# RPi-HAT_BUS-Controller_V0_4.net
KiCad netlist of a schematic drawn in EAGLE
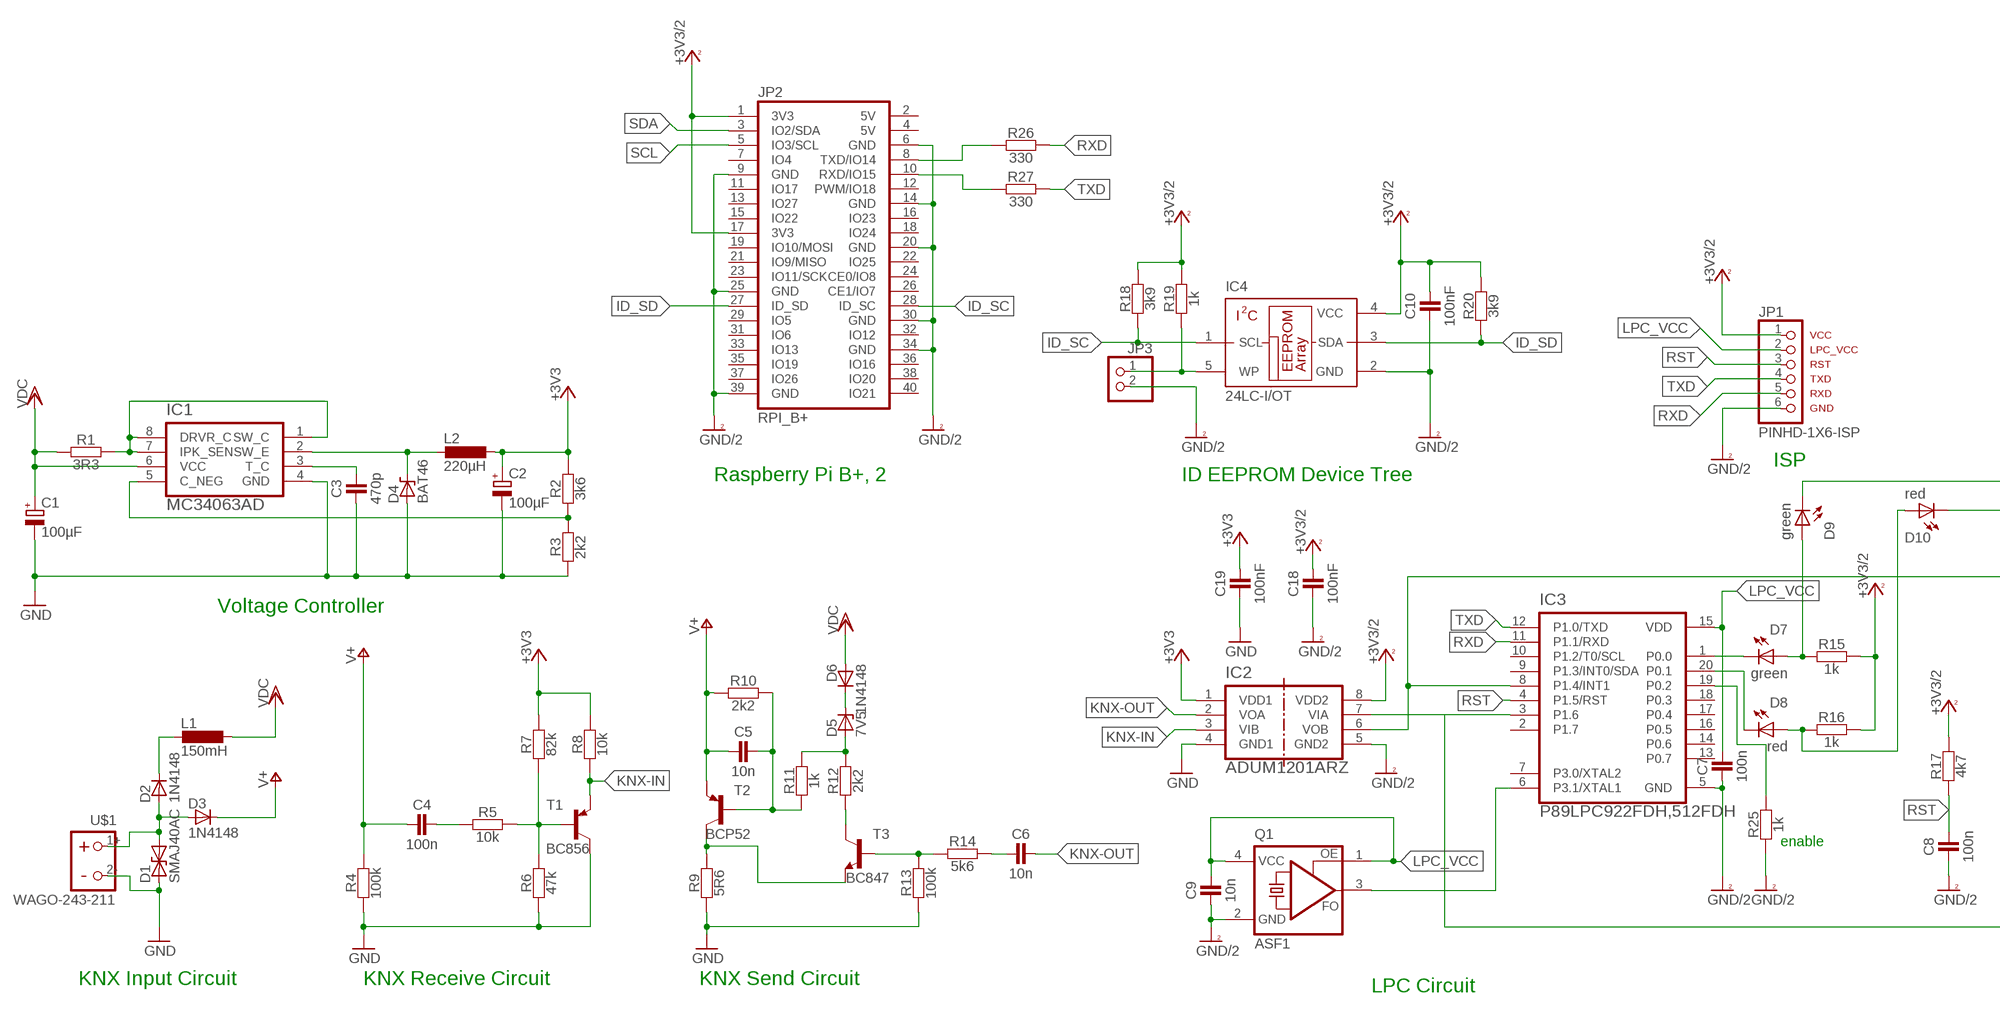
[diagram p0: schematic, sheet 1, part 1 of 2]
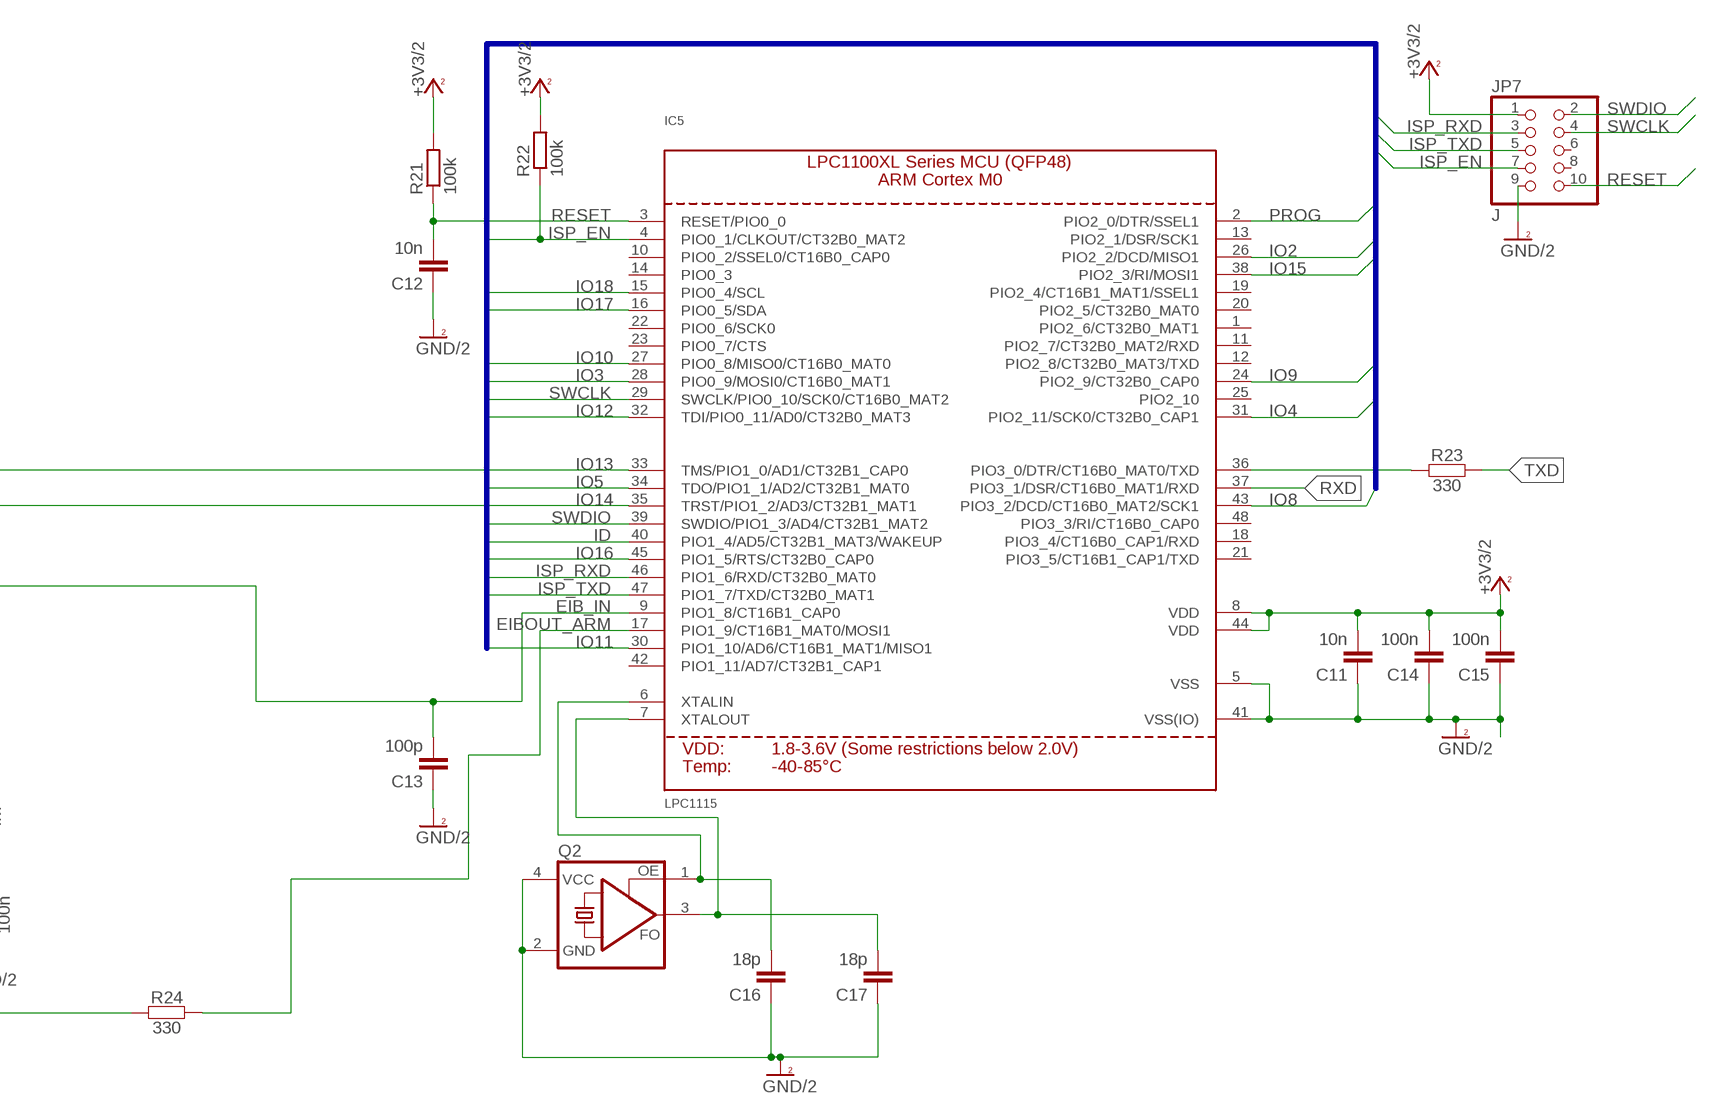
[diagram p1: schematic, sheet 1, part 2 of 2]

(export (version "E")
  (design (tool "Eeschema 10.0.6"))
  (components
    (comp (ref "C1")
      (value "100µF")
      (footprint "eagle-import:PANASONIC_D")
      (libsource (lib "eagle-import") (part "100µF,35V"))
    )
    (comp (ref "C2")
      (value "100µF")
      (footprint "eagle-import:PANASONIC_C")
      (libsource (lib "eagle-import") (part "100µF,6.3V"))
    )
    (comp (ref "C3")
      (value "470p")
      (footprint "eagle-import:R1206")
      (libsource (lib "eagle-import") (part "CAPACITORC1206"))
    )
    (comp (ref "C4")
      (value "100n")
      (footprint "eagle-import:R1206")
      (libsource (lib "eagle-import") (part "CAPACITORC1206"))
    )
    (comp (ref "C5")
      (value "10n")
      (footprint "eagle-import:R1206")
      (libsource (lib "eagle-import") (part "CAPACITORC1206"))
    )
    (comp (ref "C6")
      (value "10n")
      (footprint "eagle-import:R1206")
      (libsource (lib "eagle-import") (part "CAPACITORC1206"))
    )
    (comp (ref "C7")
      (value "100n")
      (footprint "eagle-import:R1206")
      (libsource (lib "eagle-import") (part "CAPACITORC1206"))
    )
    (comp (ref "C8")
      (value "100n")
      (footprint "eagle-import:R1206")
      (libsource (lib "eagle-import") (part "CAPACITORC1206"))
    )
    (comp (ref "C9")
      (value "10n")
      (footprint "eagle-import:R1206")
      (libsource (lib "eagle-import") (part "CAPACITORC1206"))
    )
    (comp (ref "C10")
      (value "100nF")
      (footprint "eagle-import:R1206")
      (libsource (lib "eagle-import") (part "CAPACITORC1206"))
    )
    (comp (ref "C11")
      (value "10n")
      (footprint "eagle-import:C1206")
      (libsource (lib "eagle-import") (part "C-EUC1206"))
    )
    (comp (ref "C12")
      (value "10n")
      (footprint "eagle-import:C1206")
      (libsource (lib "eagle-import") (part "C-EUC1206"))
    )
    (comp (ref "C13")
      (value "100p")
      (footprint "eagle-import:C1206")
      (libsource (lib "eagle-import") (part "C-EUC1206"))
    )
    (comp (ref "C14")
      (value "100n")
      (footprint "eagle-import:C1206")
      (libsource (lib "eagle-import") (part "C-EUC1206"))
    )
    (comp (ref "C15")
      (value "100n")
      (footprint "eagle-import:C1206")
      (libsource (lib "eagle-import") (part "C-EUC1206"))
    )
    (comp (ref "C16")
      (value "18p")
      (footprint "eagle-import:C1206")
      (libsource (lib "eagle-import") (part "C-EUC1206"))
    )
    (comp (ref "C17")
      (value "18p")
      (footprint "eagle-import:C1206")
      (libsource (lib "eagle-import") (part "C-EUC1206"))
    )
    (comp (ref "C18")
      (value "100nF")
      (footprint "eagle-import:R1206")
      (libsource (lib "eagle-import") (part "CAPACITORC1206"))
    )
    (comp (ref "C19")
      (value "100nF")
      (footprint "eagle-import:R1206")
      (libsource (lib "eagle-import") (part "CAPACITORC1206"))
    )
    (comp (ref "D1")
      (value "SMAJ40AC")
      (footprint "eagle-import:DO-214AC")
      (libsource (lib "eagle-import") (part "SMAJ40AC"))
    )
    (comp (ref "D2")
      (value "1N4148")
      (footprint "eagle-import:MINIMELF")
      (libsource (lib "eagle-import") (part "1N4148MINIMELF"))
    )
    (comp (ref "D3")
      (value "1N4148")
      (footprint "eagle-import:MINIMELF")
      (libsource (lib "eagle-import") (part "1N4148MINIMELF"))
    )
    (comp (ref "D4")
      (value "BAT46")
      (footprint "eagle-import:MINIMELF")
      (libsource (lib "eagle-import") (part "BAT46"))
    )
    (comp (ref "D5")
      (value "7V5")
      (footprint "eagle-import:MINIMELF")
      (libsource (lib "eagle-import") (part "Z-DIODE"))
    )
    (comp (ref "D6")
      (value "1N4148")
      (footprint "eagle-import:MINIMELF")
      (libsource (lib "eagle-import") (part "Diode_for_Selfbus-Projects_1N4148MINIMELF"))
    )
    (comp (ref "D7")
      (value "green")
      (footprint "eagle-import:CHIPLED_1206")
      (libsource (lib "eagle-import") (part "LED1206"))
    )
    (comp (ref "D8")
      (value "red")
      (footprint "eagle-import:CHIPLED_1206")
      (libsource (lib "eagle-import") (part "LED1206"))
    )
    (comp (ref "D9")
      (value "green")
      (footprint "eagle-import:CHIPLED_1206")
      (libsource (lib "eagle-import") (part "LED1206"))
    )
    (comp (ref "D10")
      (value "red")
      (footprint "eagle-import:CHIPLED_1206")
      (libsource (lib "eagle-import") (part "LED1206"))
    )
    (comp (ref "IC1")
      (value "MC34063AD")
      (footprint "eagle-import:SOIC127P600X175-8N")
      (libsource (lib "eagle-import") (part "MC34063AD"))
    )
    (comp (ref "IC2")
      (value "ADUM1201ARZ")
      (footprint "eagle-import:SOIC127P600X175-8N")
      (libsource (lib "eagle-import") (part "ADUM1201ARZ"))
    )
    (comp (ref "IC3")
      (value "P89LPC922FDH,512FDH")
      (footprint "eagle-import:SOP65P640X110-20N")
      (fields (field (name "MPN") "P89LPC922FDH,512"))
      (libsource (lib "eagle-import") (part "P89LPC922FDH,512FDH"))
    )
    (comp (ref "IC4")
      (value "24LC-I/OT")
      (footprint "eagle-import:SOT23-5")
      (libsource (lib "eagle-import") (part "24LC-I/OT"))
    )
    (comp (ref "IC5")
      (value "LPC1115")
      (footprint "eagle-import:LQFP48")
      (libsource (lib "eagle-import") (part "LPC1113/4/5_QFP48_XLSERIES"))
    )
    (comp (ref "JP1")
      (value "PINHD-1X6-ISP")
      (footprint "eagle-import:1X06")
      (libsource (lib "eagle-import") (part "PINHD-1X6-ISP"))
    )
    (comp (ref "JP2")
      (value "RPI_B+")
      (footprint "eagle-import:RPI-B+HAT")
      (libsource (lib "eagle-import") (part "RPI_B+"))
    )
    (comp (ref "JP3")
      (value "PINHD-1X2")
      (footprint "eagle-import:1X02")
      (libsource (lib "eagle-import") (part "PINHD-1X2"))
    )
    (comp (ref "JP7")
      (value "J")
      (footprint "eagle-import:2X05M")
      (libsource (lib "eagle-import") (part "PINHD-2X05_2.00"))
    )
    (comp (ref "L1")
      (value "150mH")
      (footprint "eagle-import:11P-L1")
      (libsource (lib "eagle-import") (part "150MH-L11PL1"))
    )
    (comp (ref "L2")
      (value "220µH")
      (footprint "eagle-import:2200-11.43")
      (libsource (lib "eagle-import") (part "220µH-SMCC11.43"))
    )
    (comp (ref "Q1")
      (value "ASF1")
      (footprint "eagle-import:ASF")
      (libsource (lib "eagle-import") (part "ASF1"))
    )
    (comp (ref "Q2")
      (value "ASFL")
      (footprint "eagle-import:ASF")
      (libsource (lib "eagle-import") (part "crystal_ASFL"))
    )
    (comp (ref "R1")
      (value "3R3")
      (footprint "eagle-import:R1206")
      (libsource (lib "eagle-import") (part "RESISTORR1206"))
    )
    (comp (ref "R2")
      (value "3k6")
      (footprint "eagle-import:R1206")
      (libsource (lib "eagle-import") (part "RESISTORR1206"))
    )
    (comp (ref "R3")
      (value "2k2")
      (footprint "eagle-import:R1206")
      (libsource (lib "eagle-import") (part "RESISTORR1206"))
    )
    (comp (ref "R4")
      (value "100k")
      (footprint "eagle-import:R1206")
      (libsource (lib "eagle-import") (part "RESISTORR1206"))
    )
    (comp (ref "R5")
      (value "10k")
      (footprint "eagle-import:R1206")
      (libsource (lib "eagle-import") (part "RESISTORR1206"))
    )
    (comp (ref "R6")
      (value "47k")
      (footprint "eagle-import:R1206")
      (libsource (lib "eagle-import") (part "RESISTORR1206"))
    )
    (comp (ref "R7")
      (value "82k")
      (footprint "eagle-import:R1206")
      (libsource (lib "eagle-import") (part "RESISTORR1206"))
    )
    (comp (ref "R8")
      (value "10k")
      (footprint "eagle-import:R1206")
      (libsource (lib "eagle-import") (part "RESISTORR1206"))
    )
    (comp (ref "R9")
      (value "5R6")
      (footprint "eagle-import:R1206")
      (libsource (lib "eagle-import") (part "RESISTORR1206"))
    )
    (comp (ref "R10")
      (value "2k2")
      (footprint "eagle-import:R1206")
      (libsource (lib "eagle-import") (part "RESISTORR1206"))
    )
    (comp (ref "R11")
      (value "1k")
      (footprint "eagle-import:R1206")
      (libsource (lib "eagle-import") (part "RESISTORR1206"))
    )
    (comp (ref "R12")
      (value "2k2")
      (footprint "eagle-import:R1206")
      (libsource (lib "eagle-import") (part "RESISTORR1206"))
    )
    (comp (ref "R13")
      (value "100k")
      (footprint "eagle-import:R1206")
      (libsource (lib "eagle-import") (part "RESISTORR1206"))
    )
    (comp (ref "R14")
      (value "5k6")
      (footprint "eagle-import:R1206")
      (libsource (lib "eagle-import") (part "RESISTORR1206"))
    )
    (comp (ref "R15")
      (value "1k")
      (footprint "eagle-import:R1206")
      (libsource (lib "eagle-import") (part "RESISTORR1206"))
    )
    (comp (ref "R16")
      (value "1k")
      (footprint "eagle-import:R1206")
      (libsource (lib "eagle-import") (part "RESISTORR1206"))
    )
    (comp (ref "R17")
      (value "4k7")
      (footprint "eagle-import:R1206")
      (libsource (lib "eagle-import") (part "RESISTORR1206"))
    )
    (comp (ref "R18")
      (value "3k9")
      (footprint "eagle-import:R1206")
      (libsource (lib "eagle-import") (part "RESISTORR1206"))
    )
    (comp (ref "R19")
      (value "1k")
      (footprint "eagle-import:R1206")
      (libsource (lib "eagle-import") (part "RESISTORR1206"))
    )
    (comp (ref "R20")
      (value "3k9")
      (footprint "eagle-import:R1206")
      (libsource (lib "eagle-import") (part "RESISTORR1206"))
    )
    (comp (ref "R21")
      (value "100k")
      (footprint "eagle-import:R1206")
      (libsource (lib "eagle-import") (part "R-EU_R1206"))
    )
    (comp (ref "R22")
      (value "100k")
      (footprint "eagle-import:R1206")
      (libsource (lib "eagle-import") (part "R-EU_R1206"))
    )
    (comp (ref "R23")
      (value "330")
      (footprint "eagle-import:R1206")
      (libsource (lib "eagle-import") (part "RESISTORR1206"))
    )
    (comp (ref "R24")
      (value "330")
      (footprint "eagle-import:R1206")
      (libsource (lib "eagle-import") (part "RESISTORR1206"))
    )
    (comp (ref "R25")
      (value "1k")
      (footprint "eagle-import:R1206")
      (libsource (lib "eagle-import") (part "RESISTORR1206"))
    )
    (comp (ref "R26")
      (value "330")
      (footprint "eagle-import:R1206")
      (libsource (lib "eagle-import") (part "RESISTORR1206"))
    )
    (comp (ref "R27")
      (value "330")
      (footprint "eagle-import:R1206")
      (libsource (lib "eagle-import") (part "RESISTORR1206"))
    )
    (comp (ref "T1")
      (value "BC856")
      (footprint "eagle-import:SOT23")
      (libsource (lib "eagle-import") (part "PNPBC856"))
    )
    (comp (ref "T2")
      (value "BCP52")
      (footprint "eagle-import:SOT223")
      (libsource (lib "eagle-import") (part "PNPBCP52"))
    )
    (comp (ref "T3")
      (value "BC847")
      (footprint "eagle-import:SOT23")
      (libsource (lib "eagle-import") (part "NPN-BC847"))
    )
    (comp (ref "U$1")
      (value "WAGO-243-211")
      (footprint "eagle-import:WAGO-243-211")
      (libsource (lib "eagle-import") (part "WAGO-243-211"))
    )
  )
  (nets
    (net (code "1") (name "+3V3") (class "Default")
      (node (ref "C19") (pin "2") (pinfunction "2_2") (pintype "passive"))
      (node (ref "C2") (pin "+") (pinfunction "+_+") (pintype "passive"))
      (node (ref "IC2") (pin "1") (pinfunction "VDD1_1") (pintype "power_in"))
      (node (ref "L2") (pin "1") (pinfunction "1_1") (pintype "passive"))
      (node (ref "R2") (pin "2") (pinfunction "2_2") (pintype "passive"))
      (node (ref "R7") (pin "2") (pinfunction "2_2") (pintype "passive"))
      (node (ref "R8") (pin "2") (pinfunction "2_2") (pintype "passive"))
    )
    (net (code "2") (name "+3V3{slash}2") (class "Default")
      (node (ref "C10") (pin "2") (pinfunction "2_2") (pintype "passive"))
      (node (ref "C11") (pin "2") (pinfunction "2_2") (pintype "passive"))
      (node (ref "C14") (pin "2") (pinfunction "2_2") (pintype "passive"))
      (node (ref "C15") (pin "2") (pinfunction "2_2") (pintype "passive"))
      (node (ref "C18") (pin "2") (pinfunction "2_2") (pintype "passive"))
      (node (ref "IC2") (pin "8") (pinfunction "VDD2_8") (pintype "power_in"))
      (node (ref "IC4") (pin "4") (pinfunction "VCC_4") (pintype "power_in"))
      (node (ref "IC5") (pin "44") (pinfunction "VDD_44") (pintype "power_in"))
      (node (ref "IC5") (pin "8") (pinfunction "VDD_8") (pintype "power_in"))
      (node (ref "JP1") (pin "1") (pinfunction "1_1") (pintype "passive"))
      (node (ref "JP2") (pin "1") (pinfunction "3V3_1") (pintype "passive"))
      (node (ref "JP2") (pin "17") (pinfunction "3V3_17") (pintype "passive"))
      (node (ref "JP7") (pin "1") (pinfunction "1_1") (pintype "passive"))
      (node (ref "R15") (pin "2") (pinfunction "2_2") (pintype "passive"))
      (node (ref "R16") (pin "2") (pinfunction "2_2") (pintype "passive"))
      (node (ref "R17") (pin "2") (pinfunction "2_2") (pintype "passive"))
      (node (ref "R18") (pin "2") (pinfunction "2_2") (pintype "passive"))
      (node (ref "R19") (pin "2") (pinfunction "2_2") (pintype "passive"))
      (node (ref "R20") (pin "2") (pinfunction "2_2") (pintype "passive"))
      (node (ref "R21") (pin "2") (pinfunction "2_2") (pintype "passive"))
      (node (ref "R22") (pin "2") (pinfunction "2_2") (pintype "passive"))
    )
    (net (code "3") (name "/EIBOUT_ARM") (class "Default")
      (node (ref "IC5") (pin "17") (pinfunction "PIO1_9/CT16B1_MAT0/MOSI1_17") (pintype "bidirectional"))
      (node (ref "R24") (pin "2") (pinfunction "2_2") (pintype "passive"))
    )
    (net (code "4") (name "/EIB_IN") (class "Default")
      (node (ref "C13") (pin "2") (pinfunction "2_2") (pintype "passive"))
      (node (ref "IC2") (pin "6") (pinfunction "VOB_6") (pintype "output"))
      (node (ref "IC3") (pin "8") (pinfunction "P1.4/INT1_8") (pintype "bidirectional"))
      (node (ref "IC5") (pin "9") (pinfunction "PIO1_8/CT16B1_CAP0_9") (pintype "bidirectional"))
    )
    (net (code "5") (name "/ID") (class "Default")
      (node (ref "IC5") (pin "40") (pinfunction "PIO1_4/AD5/CT32B1_MAT3/WAKEUP_40") (pintype "bidirectional"))
    )
    (net (code "6") (name "/IO2") (class "Default")
      (node (ref "IC5") (pin "26") (pinfunction "PIO2_2/DCD/MISO1_26") (pintype "bidirectional"))
    )
    (net (code "7") (name "/IO3") (class "Default")
      (node (ref "IC5") (pin "28") (pinfunction "PIO0_9/MOSI0/CT16B0_MAT1_28") (pintype "bidirectional"))
    )
    (net (code "8") (name "/IO4") (class "Default")
      (node (ref "IC5") (pin "31") (pinfunction "PIO2_11/SCK0/CT32B0_CAP1_31") (pintype "bidirectional"))
    )
    (net (code "9") (name "/IO5") (class "Default")
      (node (ref "IC5") (pin "34") (pinfunction "TDO/PIO1_1/AD2/CT32B1_MAT0_34") (pintype "bidirectional"))
    )
    (net (code "10") (name "/IO8") (class "Default")
      (node (ref "IC5") (pin "43") (pinfunction "PIO3_2/DCD/CT16B0_MAT2/SCK1_43") (pintype "bidirectional"))
    )
    (net (code "11") (name "/IO9") (class "Default")
      (node (ref "IC5") (pin "24") (pinfunction "PIO2_9/CT32B0_CAP0_24") (pintype "bidirectional"))
    )
    (net (code "12") (name "/IO10") (class "Default")
      (node (ref "IC5") (pin "27") (pinfunction "PIO0_8/MISO0/CT16B0_MAT0_27") (pintype "bidirectional"))
    )
    (net (code "13") (name "/IO11") (class "Default")
      (node (ref "IC5") (pin "30") (pinfunction "PIO1_10/AD6/CT16B1_MAT1/MISO1_30") (pintype "bidirectional"))
    )
    (net (code "14") (name "/IO12") (class "Default")
      (node (ref "D10") (pin "C") (pinfunction "C_C") (pintype "passive"))
      (node (ref "IC5") (pin "32") (pinfunction "TDI/PIO0_11/AD0/CT32B0_MAT3_32") (pintype "bidirectional"))
    )
    (net (code "15") (name "/IO13") (class "Default")
      (node (ref "IC5") (pin "33") (pinfunction "TMS/PIO1_0/AD1/CT32B1_CAP0_33") (pintype "bidirectional"))
    )
    (net (code "16") (name "/IO14") (class "Default")
      (node (ref "IC5") (pin "35") (pinfunction "TRST/PIO1_2/AD3/CT32B1_MAT1_35") (pintype "bidirectional"))
    )
    (net (code "17") (name "/IO15") (class "Default")
      (node (ref "D9") (pin "C") (pinfunction "C_C") (pintype "passive"))
      (node (ref "IC5") (pin "38") (pinfunction "PIO2_3/RI/MOSI1_38") (pintype "bidirectional"))
    )
    (net (code "18") (name "/IO16") (class "Default")
      (node (ref "IC5") (pin "45") (pinfunction "PIO1_5/RTS/CT32B0_CAP0_45") (pintype "bidirectional"))
    )
    (net (code "19") (name "/IO17") (class "Default")
      (node (ref "IC5") (pin "16") (pinfunction "PIO0_5/SDA_16") (pintype "bidirectional"))
    )
    (net (code "20") (name "/IO18") (class "Default")
      (node (ref "IC5") (pin "15") (pinfunction "PIO0_4/SCL_15") (pintype "bidirectional"))
    )
    (net (code "21") (name "/ISP_EN") (class "Default")
      (node (ref "IC5") (pin "4") (pinfunction "PIO0_1/CLKOUT/CT32B0_MAT2_4") (pintype "bidirectional"))
      (node (ref "JP7") (pin "7") (pinfunction "7_7") (pintype "passive"))
      (node (ref "R22") (pin "1") (pinfunction "1_1") (pintype "passive"))
    )
    (net (code "22") (name "/ISP_RXD") (class "Default")
      (node (ref "IC5") (pin "46") (pinfunction "PIO1_6/RXD/CT32B0_MAT0_46") (pintype "bidirectional"))
      (node (ref "JP7") (pin "3") (pinfunction "3_3") (pintype "passive"))
    )
    (net (code "23") (name "/ISP_TXD") (class "Default")
      (node (ref "IC5") (pin "47") (pinfunction "PIO1_7/TXD/CT32B0_MAT1_47") (pintype "bidirectional"))
      (node (ref "JP7") (pin "5") (pinfunction "5_5") (pintype "passive"))
    )
    (net (code "24") (name "/PROG") (class "Default")
      (node (ref "IC5") (pin "2") (pinfunction "PIO2_0/DTR/SSEL1_2") (pintype "bidirectional"))
    )
    (net (code "25") (name "/RESET") (class "Default")
      (node (ref "C12") (pin "2") (pinfunction "2_2") (pintype "passive"))
      (node (ref "IC5") (pin "3") (pinfunction "RESET/PIO0_0_3") (pintype "bidirectional"))
      (node (ref "JP7") (pin "10") (pinfunction "10_10") (pintype "passive"))
      (node (ref "R21") (pin "1") (pinfunction "1_1") (pintype "passive"))
    )
    (net (code "26") (name "/SWCLK") (class "Default")
      (node (ref "IC5") (pin "29") (pinfunction "SWCLK/PIO0_10/SCK0/CT16B0_MAT2_29") (pintype "bidirectional"))
      (node (ref "JP7") (pin "4") (pinfunction "4_4") (pintype "passive"))
    )
    (net (code "27") (name "/SWDIO") (class "Default")
      (node (ref "IC5") (pin "39") (pinfunction "SWDIO/PIO1_3/AD4/CT32B1_MAT2_39") (pintype "bidirectional"))
      (node (ref "JP7") (pin "2") (pinfunction "2_2") (pintype "passive"))
    )
    (net (code "28") (name "GND") (class "Default")
      (node (ref "C1") (pin "-") (pinfunction "-_-") (pintype "passive"))
      (node (ref "C19") (pin "1") (pinfunction "1_1") (pintype "passive"))
      (node (ref "C2") (pin "-") (pinfunction "-_-") (pintype "passive"))
      (node (ref "C3") (pin "1") (pinfunction "1_1") (pintype "passive"))
      (node (ref "D1") (pin "A") (pinfunction "A_A") (pintype "passive"))
      (node (ref "D4") (pin "A") (pinfunction "A_A") (pintype "passive"))
      (node (ref "IC1") (pin "4") (pinfunction "GND_4") (pintype "passive"))
      (node (ref "IC2") (pin "4") (pinfunction "GND1_4") (pintype "passive"))
      (node (ref "R13") (pin "1") (pinfunction "1_1") (pintype "passive"))
      (node (ref "R3") (pin "1") (pinfunction "1_1") (pintype "passive"))
      (node (ref "R4") (pin "1") (pinfunction "1_1") (pintype "passive"))
      (node (ref "R6") (pin "1") (pinfunction "1_1") (pintype "passive"))
      (node (ref "R9") (pin "1") (pinfunction "1_1") (pintype "passive"))
      (node (ref "T1") (pin "3") (pinfunction "C_3") (pintype "passive"))
      (node (ref "U$1") (pin "2-") (pinfunction "2-_2-") (pintype "passive"))
    )
    (net (code "29") (name "GND{slash}2") (class "Default")
      (node (ref "C10") (pin "1") (pinfunction "1_1") (pintype "passive"))
      (node (ref "C11") (pin "1") (pinfunction "1_1") (pintype "passive"))
      (node (ref "C12") (pin "1") (pinfunction "1_1") (pintype "passive"))
      (node (ref "C13") (pin "1") (pinfunction "1_1") (pintype "passive"))
      (node (ref "C14") (pin "1") (pinfunction "1_1") (pintype "passive"))
      (node (ref "C15") (pin "1") (pinfunction "1_1") (pintype "passive"))
      (node (ref "C16") (pin "1") (pinfunction "1_1") (pintype "passive"))
      (node (ref "C17") (pin "1") (pinfunction "1_1") (pintype "passive"))
      (node (ref "C18") (pin "1") (pinfunction "1_1") (pintype "passive"))
      (node (ref "C7") (pin "1") (pinfunction "1_1") (pintype "passive"))
      (node (ref "C8") (pin "1") (pinfunction "1_1") (pintype "passive"))
      (node (ref "C9") (pin "1") (pinfunction "1_1") (pintype "passive"))
      (node (ref "IC2") (pin "5") (pinfunction "GND2_5") (pintype "passive"))
      (node (ref "IC3") (pin "5") (pinfunction "GND_5") (pintype "passive"))
      (node (ref "IC4") (pin "2") (pinfunction "GND_2") (pintype "power_in"))
      (node (ref "IC5") (pin "41") (pinfunction "VSS(IO)_41") (pintype "power_in"))
      (node (ref "IC5") (pin "5") (pinfunction "VSS_5") (pintype "power_in"))
      (node (ref "JP1") (pin "6") (pinfunction "6_6") (pintype "passive"))
      (node (ref "JP2") (pin "14") (pinfunction "GND_14") (pintype "passive"))
      (node (ref "JP2") (pin "20") (pinfunction "GND_20") (pintype "passive"))
      (node (ref "JP2") (pin "25") (pinfunction "GND_25") (pintype "passive"))
      (node (ref "JP2") (pin "30") (pinfunction "GND_30") (pintype "bidirectional"))
      (node (ref "JP2") (pin "34") (pinfunction "GND_34") (pintype "bidirectional"))
      (node (ref "JP2") (pin "39") (pinfunction "GND_39") (pintype "bidirectional"))
      (node (ref "JP2") (pin "6") (pinfunction "GND_6") (pintype "passive"))
      (node (ref "JP2") (pin "9") (pinfunction "GND_9") (pintype "passive"))
      (node (ref "JP3") (pin "2") (pinfunction "2_2") (pintype "passive"))
      (node (ref "JP7") (pin "9") (pinfunction "9_9") (pintype "passive"))
      (node (ref "Q1") (pin "2") (pinfunction "GND_2") (pintype "power_in"))
      (node (ref "Q2") (pin "2") (pinfunction "GND_2") (pintype "power_in"))
      (node (ref "Q2") (pin "4") (pinfunction "VCC_4") (pintype "power_in"))
      (node (ref "R25") (pin "1") (pinfunction "1_1") (pintype "passive"))
    )
    (net (code "30") (name "ID_SC") (class "Default")
      (node (ref "IC4") (pin "1") (pinfunction "SCL_1") (pintype "bidirectional"))
      (node (ref "JP2") (pin "28") (pinfunction "ID_SC_28") (pintype "bidirectional"))
      (node (ref "R18") (pin "1") (pinfunction "1_1") (pintype "passive"))
    )
    (net (code "31") (name "ID_SD") (class "Default")
      (node (ref "IC4") (pin "3") (pinfunction "SDA_3") (pintype "bidirectional"))
      (node (ref "JP2") (pin "27") (pinfunction "ID_SD_27") (pintype "bidirectional"))
      (node (ref "R20") (pin "1") (pinfunction "1_1") (pintype "passive"))
    )
    (net (code "32") (name "KNX-IN") (class "Default")
      (node (ref "IC2") (pin "3") (pinfunction "VIB_3") (pintype "input"))
      (node (ref "R8") (pin "1") (pinfunction "1_1") (pintype "passive"))
      (node (ref "T1") (pin "2") (pinfunction "E_2") (pintype "passive"))
    )
    (net (code "33") (name "KNX-OUT") (class "Default")
      (node (ref "C6") (pin "2") (pinfunction "2_2") (pintype "passive"))
      (node (ref "IC2") (pin "2") (pinfunction "VOA_2") (pintype "output"))
    )
    (net (code "34") (name "LPC_VCC") (class "Default")
      (node (ref "C7") (pin "2") (pinfunction "2_2") (pintype "passive"))
      (node (ref "C9") (pin "2") (pinfunction "2_2") (pintype "passive"))
      (node (ref "IC3") (pin "15") (pinfunction "VDD_15") (pintype "power_in"))
      (node (ref "JP1") (pin "2") (pinfunction "2_2") (pintype "passive"))
      (node (ref "Q1") (pin "1") (pinfunction "OE_1") (pintype "input"))
      (node (ref "Q1") (pin "4") (pinfunction "VCC_4") (pintype "power_in"))
    )
    (net (code "35") (name "Net-(C4-Pad2)") (class "Default")
      (node (ref "C4") (pin "2") (pinfunction "2_2") (pintype "passive"))
      (node (ref "R5") (pin "1") (pinfunction "1_1") (pintype "passive"))
    )
    (net (code "36") (name "Net-(C6-Pad1)") (class "Default")
      (node (ref "C6") (pin "1") (pinfunction "1_1") (pintype "passive"))
      (node (ref "R14") (pin "2") (pinfunction "2_2") (pintype "passive"))
    )
    (net (code "37") (name "Net-(D1-PadC)") (class "Default")
      (node (ref "D1") (pin "C") (pinfunction "C_C") (pintype "passive"))
      (node (ref "D2") (pin "A") (pinfunction "A_A") (pintype "passive"))
      (node (ref "D3") (pin "A") (pinfunction "A_A") (pintype "passive"))
      (node (ref "U$1") (pin "1+") (pinfunction "1+_1+") (pintype "passive"))
    )
    (net (code "38") (name "Net-(D2-PadC)") (class "Default")
      (node (ref "D2") (pin "C") (pinfunction "C_C") (pintype "passive"))
      (node (ref "L1") (pin "2") (pinfunction "2_2") (pintype "passive"))
    )
    (net (code "39") (name "Net-(D5-PadA)") (class "Default")
      (node (ref "D5") (pin "A") (pinfunction "A_A") (pintype "passive"))
      (node (ref "R11") (pin "2") (pinfunction "2_2") (pintype "passive"))
      (node (ref "R12") (pin "2") (pinfunction "2_2") (pintype "passive"))
    )
    (net (code "40") (name "Net-(D5-PadC)") (class "Default")
      (node (ref "D5") (pin "C") (pinfunction "C_C") (pintype "passive"))
      (node (ref "D6") (pin "C") (pinfunction "C_C") (pintype "passive"))
    )
    (net (code "41") (name "Net-(D7-PadA)") (class "Default")
      (node (ref "D7") (pin "A") (pinfunction "A_A") (pintype "passive"))
      (node (ref "D9") (pin "A") (pinfunction "A_A") (pintype "passive"))
      (node (ref "R15") (pin "1") (pinfunction "1_1") (pintype "passive"))
    )
    (net (code "42") (name "Net-(D10-PadA)") (class "Default")
      (node (ref "D10") (pin "A") (pinfunction "A_A") (pintype "passive"))
      (node (ref "D8") (pin "A") (pinfunction "A_A") (pintype "passive"))
      (node (ref "R16") (pin "1") (pinfunction "1_1") (pintype "passive"))
    )
    (net (code "43") (name "Net-(IC1-C_NEG)") (class "Default")
      (node (ref "IC1") (pin "5") (pinfunction "C_NEG_5") (pintype "input"))
      (node (ref "R2") (pin "1") (pinfunction "1_1") (pintype "passive"))
      (node (ref "R3") (pin "2") (pinfunction "2_2") (pintype "passive"))
    )
    (net (code "44") (name "Net-(IC1-DRVR_C)") (class "Default")
      (node (ref "IC1") (pin "1") (pinfunction "SW_C_1") (pintype "output"))
      (node (ref "IC1") (pin "7") (pinfunction "IPK_SEN_7") (pintype "input"))
      (node (ref "IC1") (pin "8") (pinfunction "DRVR_C_8") (pintype "input"))
      (node (ref "R1") (pin "2") (pinfunction "2_2") (pintype "passive"))
    )
    (net (code "45") (name "Net-(IC1-SW_E)") (class "Default")
      (node (ref "D4") (pin "C") (pinfunction "C_C") (pintype "passive"))
      (node (ref "IC1") (pin "2") (pinfunction "SW_E_2") (pintype "output"))
      (node (ref "L2") (pin "2") (pinfunction "2_2") (pintype "passive"))
    )
    (net (code "46") (name "Net-(IC1-T_C)") (class "Default")
      (node (ref "C3") (pin "2") (pinfunction "2_2") (pintype "passive"))
      (node (ref "IC1") (pin "3") (pinfunction "T_C_3") (pintype "output"))
    )
    (net (code "47") (name "Net-(IC2-VIA)") (class "Default")
      (node (ref "IC2") (pin "7") (pinfunction "VIA_7") (pintype "input"))
      (node (ref "IC3") (pin "3") (pinfunction "P1.6_3") (pintype "bidirectional"))
      (node (ref "R24") (pin "1") (pinfunction "1_1") (pintype "passive"))
    )
    (net (code "48") (name "Net-(IC3-P0.0)") (class "Default")
      (node (ref "D7") (pin "C") (pinfunction "C_C") (pintype "passive"))
      (node (ref "IC3") (pin "1") (pinfunction "P0.0_1") (pintype "bidirectional"))
    )
    (net (code "49") (name "Net-(IC3-P0.1)") (class "Default")
      (node (ref "D8") (pin "C") (pinfunction "C_C") (pintype "passive"))
      (node (ref "IC3") (pin "20") (pinfunction "P0.1_20") (pintype "bidirectional"))
    )
    (net (code "50") (name "Net-(IC3-P0.2)") (class "Default")
      (node (ref "IC3") (pin "19") (pinfunction "P0.2_19") (pintype "bidirectional"))
      (node (ref "R25") (pin "2") (pinfunction "2_2") (pintype "passive"))
    )
    (net (code "51") (name "Net-(IC3-P3.1{slash}XTAL1)") (class "Default")
      (node (ref "IC3") (pin "6") (pinfunction "P3.1/XTAL1_6") (pintype "bidirectional"))
      (node (ref "Q1") (pin "3") (pinfunction "FO_3") (pintype "output"))
    )
    (net (code "52") (name "Net-(IC4-WP)") (class "Default")
      (node (ref "IC4") (pin "5") (pinfunction "WP_5") (pintype "bidirectional"))
      (node (ref "JP3") (pin "1") (pinfunction "1_1") (pintype "passive"))
      (node (ref "R19") (pin "1") (pinfunction "1_1") (pintype "passive"))
    )
    (net (code "53") (name "Net-(IC5-PIO3_0{slash}DTR{slash}CT16B0_MAT0{slash}TXD)") (class "Default")
      (node (ref "IC5") (pin "36") (pinfunction "PIO3_0/DTR/CT16B0_MAT0/TXD_36") (pintype "bidirectional"))
      (node (ref "R23") (pin "1") (pinfunction "1_1") (pintype "passive"))
    )
    (net (code "54") (name "Net-(IC5-XTALIN)") (class "Default")
      (node (ref "C16") (pin "2") (pinfunction "2_2") (pintype "passive"))
      (node (ref "IC5") (pin "6") (pinfunction "XTALIN_6") (pintype "input"))
      (node (ref "Q2") (pin "1") (pinfunction "OE_1") (pintype "input"))
    )
    (net (code "55") (name "Net-(IC5-XTALOUT)") (class "Default")
      (node (ref "C17") (pin "2") (pinfunction "2_2") (pintype "passive"))
      (node (ref "IC5") (pin "7") (pinfunction "XTALOUT_7") (pintype "output"))
      (node (ref "Q2") (pin "3") (pinfunction "FO_3") (pintype "output"))
    )
    (net (code "56") (name "Net-(JP2-RXD{slash}IO15)") (class "Default")
      (node (ref "JP2") (pin "10") (pinfunction "RXD/IO15_10") (pintype "passive"))
      (node (ref "R27") (pin "1") (pinfunction "1_1") (pintype "passive"))
    )
    (net (code "57") (name "Net-(JP2-TXD{slash}IO14)") (class "Default")
      (node (ref "JP2") (pin "8") (pinfunction "TXD/IO14_8") (pintype "passive"))
      (node (ref "R26") (pin "1") (pinfunction "1_1") (pintype "passive"))
    )
    (net (code "58") (name "Net-(T1-B)") (class "Default")
      (node (ref "R5") (pin "2") (pinfunction "2_2") (pintype "passive"))
      (node (ref "R6") (pin "2") (pinfunction "2_2") (pintype "passive"))
      (node (ref "R7") (pin "1") (pinfunction "1_1") (pintype "passive"))
      (node (ref "T1") (pin "1") (pinfunction "B_1") (pintype "passive"))
    )
    (net (code "59") (name "Net-(T2-B)") (class "Default")
      (node (ref "C5") (pin "2") (pinfunction "2_2") (pintype "passive"))
      (node (ref "R10") (pin "2") (pinfunction "2_2") (pintype "passive"))
      (node (ref "R11") (pin "1") (pinfunction "1_1") (pintype "passive"))
      (node (ref "T2") (pin "1") (pinfunction "B_1") (pintype "passive"))
    )
    (net (code "60") (name "Net-(T3-B)") (class "Default")
      (node (ref "R13") (pin "2") (pinfunction "2_2") (pintype "passive"))
      (node (ref "R14") (pin "1") (pinfunction "1_1") (pintype "passive"))
      (node (ref "T3") (pin "1") (pinfunction "B_1") (pintype "passive"))
    )
    (net (code "61") (name "Net-(T3-C)") (class "Default")
      (node (ref "R12") (pin "1") (pinfunction "1_1") (pintype "passive"))
      (node (ref "T3") (pin "3") (pinfunction "C_3") (pintype "passive"))
    )
    (net (code "62") (name "Net-(T3-E)") (class "Default")
      (node (ref "R9") (pin "2") (pinfunction "2_2") (pintype "passive"))
      (node (ref "T2") (pin "2") (pinfunction "C_2") (pintype "passive"))
      (node (ref "T2") (pin "4") (pinfunction "C_4") (pintype "passive"))
      (node (ref "T3") (pin "2") (pinfunction "E_2") (pintype "passive"))
    )
    (net (code "63") (name "RST") (class "Default")
      (node (ref "C8") (pin "2") (pinfunction "2_2") (pintype "passive"))
      (node (ref "IC3") (pin "4") (pinfunction "P1.5/RST_4") (pintype "input"))
      (node (ref "JP1") (pin "3") (pinfunction "3_3") (pintype "passive"))
      (node (ref "R17") (pin "1") (pinfunction "1_1") (pintype "passive"))
    )
    (net (code "64") (name "RXD") (class "Default")
      (node (ref "IC3") (pin "11") (pinfunction "P1.1/RXD_11") (pintype "bidirectional"))
      (node (ref "IC5") (pin "37") (pinfunction "PIO3_1/DSR/CT16B0_MAT1/RXD_37") (pintype "bidirectional"))
      (node (ref "JP1") (pin "5") (pinfunction "5_5") (pintype "passive"))
    )
    (net (code "65") (name "SCL") (class "Default")
      (node (ref "JP2") (pin "5") (pinfunction "IO3/SCL_5") (pintype "passive"))
    )
    (net (code "66") (name "SDA") (class "Default")
      (node (ref "JP2") (pin "3") (pinfunction "IO2/SDA_3") (pintype "passive"))
    )
    (net (code "67") (name "TXD") (class "Default")
      (node (ref "IC3") (pin "12") (pinfunction "P1.0/TXD_12") (pintype "bidirectional"))
      (node (ref "JP1") (pin "4") (pinfunction "4_4") (pintype "passive"))
      (node (ref "R23") (pin "2") (pinfunction "2_2") (pintype "passive"))
    )
    (net (code "68") (name "V+") (class "Default")
      (node (ref "C4") (pin "1") (pinfunction "1_1") (pintype "passive"))
      (node (ref "C5") (pin "1") (pinfunction "1_1") (pintype "passive"))
      (node (ref "D3") (pin "C") (pinfunction "C_C") (pintype "passive"))
      (node (ref "R10") (pin "1") (pinfunction "1_1") (pintype "passive"))
      (node (ref "R4") (pin "2") (pinfunction "2_2") (pintype "passive"))
      (node (ref "T2") (pin "3") (pinfunction "E_3") (pintype "passive"))
    )
    (net (code "69") (name "VDC") (class "Default")
      (node (ref "C1") (pin "+") (pinfunction "+_+") (pintype "passive"))
      (node (ref "D6") (pin "A") (pinfunction "A_A") (pintype "passive"))
      (node (ref "IC1") (pin "6") (pinfunction "VCC_6") (pintype "power_in"))
      (node (ref "L1") (pin "1") (pinfunction "1_1") (pintype "passive"))
      (node (ref "R1") (pin "1") (pinfunction "1_1") (pintype "passive"))
    )
    (net (code "70") (name "unconnected-(IC3-P0.3-Pad18)") (class "Default")
      (node (ref "IC3") (pin "18") (pinfunction "P0.3_18") (pintype "bidirectional"))
    )
    (net (code "71") (name "unconnected-(IC3-P0.4-Pad17)") (class "Default")
      (node (ref "IC3") (pin "17") (pinfunction "P0.4_17") (pintype "bidirectional"))
    )
    (net (code "72") (name "unconnected-(IC3-P0.5-Pad16)") (class "Default")
      (node (ref "IC3") (pin "16") (pinfunction "P0.5_16") (pintype "bidirectional"))
    )
    (net (code "73") (name "unconnected-(IC3-P0.6-Pad14)") (class "Default")
      (node (ref "IC3") (pin "14") (pinfunction "P0.6_14") (pintype "bidirectional"))
    )
    (net (code "74") (name "unconnected-(IC3-P0.7-Pad13)") (class "Default")
      (node (ref "IC3") (pin "13") (pinfunction "P0.7_13") (pintype "passive"))
    )
    (net (code "75") (name "unconnected-(IC3-P1.2{slash}T0{slash}SCL-Pad10)") (class "Default")
      (node (ref "IC3") (pin "10") (pinfunction "P1.2/T0/SCL_10") (pintype "bidirectional"))
    )
    (net (code "76") (name "unconnected-(IC3-P1.3{slash}INT0{slash}SDA-Pad9)") (class "Default")
      (node (ref "IC3") (pin "9") (pinfunction "P1.3/INT0/SDA_9") (pintype "bidirectional"))
    )
    (net (code "77") (name "unconnected-(IC3-P1.7-Pad2)") (class "Default")
      (node (ref "IC3") (pin "2") (pinfunction "P1.7_2") (pintype "bidirectional"))
    )
    (net (code "78") (name "unconnected-(IC3-P3.0{slash}XTAL2-Pad7)") (class "Default")
      (node (ref "IC3") (pin "7") (pinfunction "P3.0/XTAL2_7") (pintype "bidirectional"))
    )
    (net (code "79") (name "unconnected-(IC5-PIO0_2{slash}SSEL0{slash}CT16B0_CAP0-Pad10)") (class "Default")
      (node (ref "IC5") (pin "10") (pinfunction "PIO0_2/SSEL0/CT16B0_CAP0_10") (pintype "bidirectional"))
    )
    (net (code "80") (name "unconnected-(IC5-PIO0_3-Pad14)") (class "Default")
      (node (ref "IC5") (pin "14") (pinfunction "PIO0_3_14") (pintype "bidirectional"))
    )
    (net (code "81") (name "unconnected-(IC5-PIO0_6{slash}SCK0-Pad22)") (class "Default")
      (node (ref "IC5") (pin "22") (pinfunction "PIO0_6/SCK0_22") (pintype "bidirectional"))
    )
    (net (code "82") (name "unconnected-(IC5-PIO0_7{slash}CTS-Pad23)") (class "Default")
      (node (ref "IC5") (pin "23") (pinfunction "PIO0_7/CTS_23") (pintype "bidirectional"))
    )
    (net (code "83") (name "unconnected-(IC5-PIO1_11{slash}AD7{slash}CT32B1_CAP1-Pad42)") (class "Default")
      (node (ref "IC5") (pin "42") (pinfunction "PIO1_11/AD7/CT32B1_CAP1_42") (pintype "bidirectional"))
    )
    (net (code "84") (name "unconnected-(IC5-PIO2_1{slash}DSR{slash}SCK1-Pad13)") (class "Default")
      (node (ref "IC5") (pin "13") (pinfunction "PIO2_1/DSR/SCK1_13") (pintype "bidirectional"))
    )
    (net (code "85") (name "unconnected-(IC5-PIO2_4{slash}CT16B1_MAT1{slash}SSEL1-Pad19)") (class "Default")
      (node (ref "IC5") (pin "19") (pinfunction "PIO2_4/CT16B1_MAT1/SSEL1_19") (pintype "bidirectional"))
    )
    (net (code "86") (name "unconnected-(IC5-PIO2_5{slash}CT32B0_MAT0-Pad20)") (class "Default")
      (node (ref "IC5") (pin "20") (pinfunction "PIO2_5/CT32B0_MAT0_20") (pintype "bidirectional"))
    )
    (net (code "87") (name "unconnected-(IC5-PIO2_6{slash}CT32B0_MAT1-Pad1)") (class "Default")
      (node (ref "IC5") (pin "1") (pinfunction "PIO2_6/CT32B0_MAT1_1") (pintype "bidirectional"))
    )
    (net (code "88") (name "unconnected-(IC5-PIO2_7{slash}CT32B0_MAT2{slash}RXD-Pad11)") (class "Default")
      (node (ref "IC5") (pin "11") (pinfunction "PIO2_7/CT32B0_MAT2/RXD_11") (pintype "bidirectional"))
    )
    (net (code "89") (name "unconnected-(IC5-PIO2_8{slash}CT32B0_MAT3{slash}TXD-Pad12)") (class "Default")
      (node (ref "IC5") (pin "12") (pinfunction "PIO2_8/CT32B0_MAT3/TXD_12") (pintype "bidirectional"))
    )
    (net (code "90") (name "unconnected-(IC5-PIO2_10-Pad25)") (class "Default")
      (node (ref "IC5") (pin "25") (pinfunction "PIO2_10_25") (pintype "bidirectional"))
    )
    (net (code "91") (name "unconnected-(IC5-PIO3_3{slash}RI{slash}CT16B0_CAP0-Pad48)") (class "Default")
      (node (ref "IC5") (pin "48") (pinfunction "PIO3_3/RI/CT16B0_CAP0_48") (pintype "bidirectional"))
    )
    (net (code "92") (name "unconnected-(IC5-PIO3_4{slash}CT16B0_CAP1{slash}RXD-Pad18)") (class "Default")
      (node (ref "IC5") (pin "18") (pinfunction "PIO3_4/CT16B0_CAP1/RXD_18") (pintype "bidirectional"))
    )
    (net (code "93") (name "unconnected-(IC5-PIO3_5{slash}CT16B1_CAP1{slash}TXD-Pad21)") (class "Default")
      (node (ref "IC5") (pin "21") (pinfunction "PIO3_5/CT16B1_CAP1/TXD_21") (pintype "bidirectional"))
    )
    (net (code "94") (name "unconnected-(JP2-5V-Pad2)") (class "Default")
      (node (ref "JP2") (pin "2") (pinfunction "5V_2") (pintype "passive"))
    )
    (net (code "95") (name "unconnected-(JP2-5V-Pad4)") (class "Default")
      (node (ref "JP2") (pin "4") (pinfunction "5V_4") (pintype "passive"))
    )
    (net (code "96") (name "unconnected-(JP2-CE0{slash}IO8-Pad24)") (class "Default")
      (node (ref "JP2") (pin "24") (pinfunction "CE0/IO8_24") (pintype "passive"))
    )
    (net (code "97") (name "unconnected-(JP2-CE1{slash}IO7-Pad26)") (class "Default")
      (node (ref "JP2") (pin "26") (pinfunction "CE1/IO7_26") (pintype "passive"))
    )
    (net (code "98") (name "unconnected-(JP2-IO4-Pad7)") (class "Default")
      (node (ref "JP2") (pin "7") (pinfunction "IO4_7") (pintype "passive"))
    )
    (net (code "99") (name "unconnected-(JP2-IO5-Pad29)") (class "Default")
      (node (ref "JP2") (pin "29") (pinfunction "IO5_29") (pintype "bidirectional"))
    )
    (net (code "100") (name "unconnected-(JP2-IO6-Pad31)") (class "Default")
      (node (ref "JP2") (pin "31") (pinfunction "IO6_31") (pintype "bidirectional"))
    )
    (net (code "101") (name "unconnected-(JP2-IO9{slash}MISO-Pad21)") (class "Default")
      (node (ref "JP2") (pin "21") (pinfunction "IO9/MISO_21") (pintype "passive"))
    )
    (net (code "102") (name "unconnected-(JP2-IO10{slash}MOSI-Pad19)") (class "Default")
      (node (ref "JP2") (pin "19") (pinfunction "IO10/MOSI_19") (pintype "passive"))
    )
    (net (code "103") (name "unconnected-(JP2-IO11{slash}SCK-Pad23)") (class "Default")
      (node (ref "JP2") (pin "23") (pinfunction "IO11/SCK_23") (pintype "passive"))
    )
    (net (code "104") (name "unconnected-(JP2-IO12-Pad32)") (class "Default")
      (node (ref "JP2") (pin "32") (pinfunction "IO12_32") (pintype "bidirectional"))
    )
    (net (code "105") (name "unconnected-(JP2-IO13-Pad33)") (class "Default")
      (node (ref "JP2") (pin "33") (pinfunction "IO13_33") (pintype "bidirectional"))
    )
    (net (code "106") (name "unconnected-(JP2-IO16-Pad36)") (class "Default")
      (node (ref "JP2") (pin "36") (pinfunction "IO16_36") (pintype "bidirectional"))
    )
    (net (code "107") (name "unconnected-(JP2-IO17-Pad11)") (class "Default")
      (node (ref "JP2") (pin "11") (pinfunction "IO17_11") (pintype "passive"))
    )
    (net (code "108") (name "unconnected-(JP2-IO19-Pad35)") (class "Default")
      (node (ref "JP2") (pin "35") (pinfunction "IO19_35") (pintype "bidirectional"))
    )
    (net (code "109") (name "unconnected-(JP2-IO20-Pad38)") (class "Default")
      (node (ref "JP2") (pin "38") (pinfunction "IO20_38") (pintype "bidirectional"))
    )
    (net (code "110") (name "unconnected-(JP2-IO21-Pad40)") (class "Default")
      (node (ref "JP2") (pin "40") (pinfunction "IO21_40") (pintype "bidirectional"))
    )
    (net (code "111") (name "unconnected-(JP2-IO22-Pad15)") (class "Default")
      (node (ref "JP2") (pin "15") (pinfunction "IO22_15") (pintype "passive"))
    )
    (net (code "112") (name "unconnected-(JP2-IO23-Pad16)") (class "Default")
      (node (ref "JP2") (pin "16") (pinfunction "IO23_16") (pintype "passive"))
    )
    (net (code "113") (name "unconnected-(JP2-IO24-Pad18)") (class "Default")
      (node (ref "JP2") (pin "18") (pinfunction "IO24_18") (pintype "passive"))
    )
    (net (code "114") (name "unconnected-(JP2-IO25-Pad22)") (class "Default")
      (node (ref "JP2") (pin "22") (pinfunction "IO25_22") (pintype "passive"))
    )
    (net (code "115") (name "unconnected-(JP2-IO26-Pad37)") (class "Default")
      (node (ref "JP2") (pin "37") (pinfunction "IO26_37") (pintype "bidirectional"))
    )
    (net (code "116") (name "unconnected-(JP2-IO27-Pad13)") (class "Default")
      (node (ref "JP2") (pin "13") (pinfunction "IO27_13") (pintype "passive"))
    )
    (net (code "117") (name "unconnected-(JP2-PWM{slash}IO18-Pad12)") (class "Default")
      (node (ref "JP2") (pin "12") (pinfunction "PWM/IO18_12") (pintype "passive"))
    )
    (net (code "118") (name "unconnected-(JP7-Pad6)") (class "Default")
      (node (ref "JP7") (pin "6") (pinfunction "6_6") (pintype "passive"))
    )
    (net (code "119") (name "unconnected-(JP7-Pad8)") (class "Default")
      (node (ref "JP7") (pin "8") (pinfunction "8_8") (pintype "passive"))
    )
    (net (code "120") (name "unconnected-(R26-Pad2)") (class "Default")
      (node (ref "R26") (pin "2") (pinfunction "2_2") (pintype "passive"))
    )
    (net (code "121") (name "unconnected-(R27-Pad2)") (class "Default")
      (node (ref "R27") (pin "2") (pinfunction "2_2") (pintype "passive"))
    )
  )
)
